# Motor_Board_Connector.net
KiCad netlist of a schematic drawn in Altium Designer
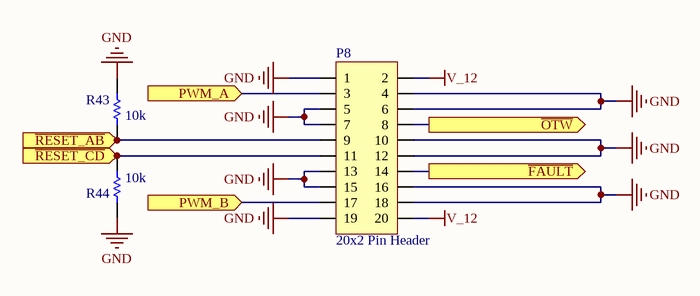
[diagram p0: Motor_Board_Connector.SchDoc]

(export (version "E")
  (design (tool "Eeschema 10.0.6"))
  (components
    (comp (ref "P8")
      (value "20x2 Pin Header")
      (footprint "G_HDR2X10")
      (description "CONN HEADER 20 POS STRGHT GOLD")
      (fields (field (name "MANUFACTURER") "3M") (field (name "PART NUMBER") "JP_20x2 PIN_HDR_WALL"))
      (libsource (lib "ENEL429_4") (part "JP_20x2 PIN_HDR_WALL"))
    )
    (comp (ref "R43")
      (value "10k")
      (footprint "0603")
      (description "RES 10.0K OHM 1/10W 1% 0603 SMD")
      (fields (field (name "MANUFACTURER") "Yageo") (field (name "PART NUMBER") "RS_10k 0603"))
      (libsource (lib "ENEL429_4") (part "RS_10k 0603"))
    )
    (comp (ref "R44")
      (value "10k")
      (footprint "0603")
      (description "RES 10.0K OHM 1/10W 1% 0603 SMD")
      (fields (field (name "MANUFACTURER") "Yageo") (field (name "PART NUMBER") "RS_10k 0603"))
      (libsource (lib "ENEL429_4") (part "RS_10k 0603"))
    )
  )
  (nets
    (net (code "1") (name "/PWM_A") (class "Default")
      (node (ref "P8") (pin "3") (pinfunction "3_3") (pintype "passive"))
    )
    (net (code "2") (name "/PWM_B") (class "Default")
      (node (ref "P8") (pin "17") (pinfunction "17_17") (pintype "passive"))
    )
    (net (code "3") (name "/~{FAULT}") (class "Default")
      (node (ref "P8") (pin "14") (pinfunction "14_14") (pintype "passive"))
    )
    (net (code "4") (name "/~{OTW}") (class "Default")
      (node (ref "P8") (pin "8") (pinfunction "8_8") (pintype "passive"))
    )
    (net (code "5") (name "/~{RESET_AB}") (class "Default")
      (node (ref "P8") (pin "9") (pinfunction "9_9") (pintype "passive"))
      (node (ref "R43") (pin "1") (pinfunction "1_1") (pintype "passive"))
    )
    (net (code "6") (name "/~{RESET_CD}") (class "Default")
      (node (ref "P8") (pin "11") (pinfunction "11_11") (pintype "passive"))
      (node (ref "R44") (pin "2") (pinfunction "2_2") (pintype "passive"))
    )
    (net (code "7") (name "GND") (class "Default")
      (node (ref "P8") (pin "1") (pinfunction "1_1") (pintype "passive"))
      (node (ref "P8") (pin "10") (pinfunction "10_10") (pintype "passive"))
      (node (ref "P8") (pin "12") (pinfunction "12_12") (pintype "passive"))
      (node (ref "P8") (pin "13") (pinfunction "13_13") (pintype "passive"))
      (node (ref "P8") (pin "15") (pinfunction "15_15") (pintype "passive"))
      (node (ref "P8") (pin "16") (pinfunction "16_16") (pintype "passive"))
      (node (ref "P8") (pin "18") (pinfunction "18_18") (pintype "passive"))
      (node (ref "P8") (pin "19") (pinfunction "19_19") (pintype "passive"))
      (node (ref "P8") (pin "4") (pinfunction "4_4") (pintype "passive"))
      (node (ref "P8") (pin "5") (pinfunction "5_5") (pintype "passive"))
      (node (ref "P8") (pin "6") (pinfunction "6_6") (pintype "passive"))
      (node (ref "P8") (pin "7") (pinfunction "7_7") (pintype "passive"))
      (node (ref "R43") (pin "2") (pinfunction "2_2") (pintype "passive"))
      (node (ref "R44") (pin "1") (pinfunction "1_1") (pintype "passive"))
    )
    (net (code "8") (name "V_12") (class "Default")
      (node (ref "P8") (pin "2") (pinfunction "2_2") (pintype "passive"))
      (node (ref "P8") (pin "20") (pinfunction "20_20") (pintype "passive"))
    )
  )
)
